# Sensor_Board.net
KiCad netlist of a schematic drawn in Altium Designer
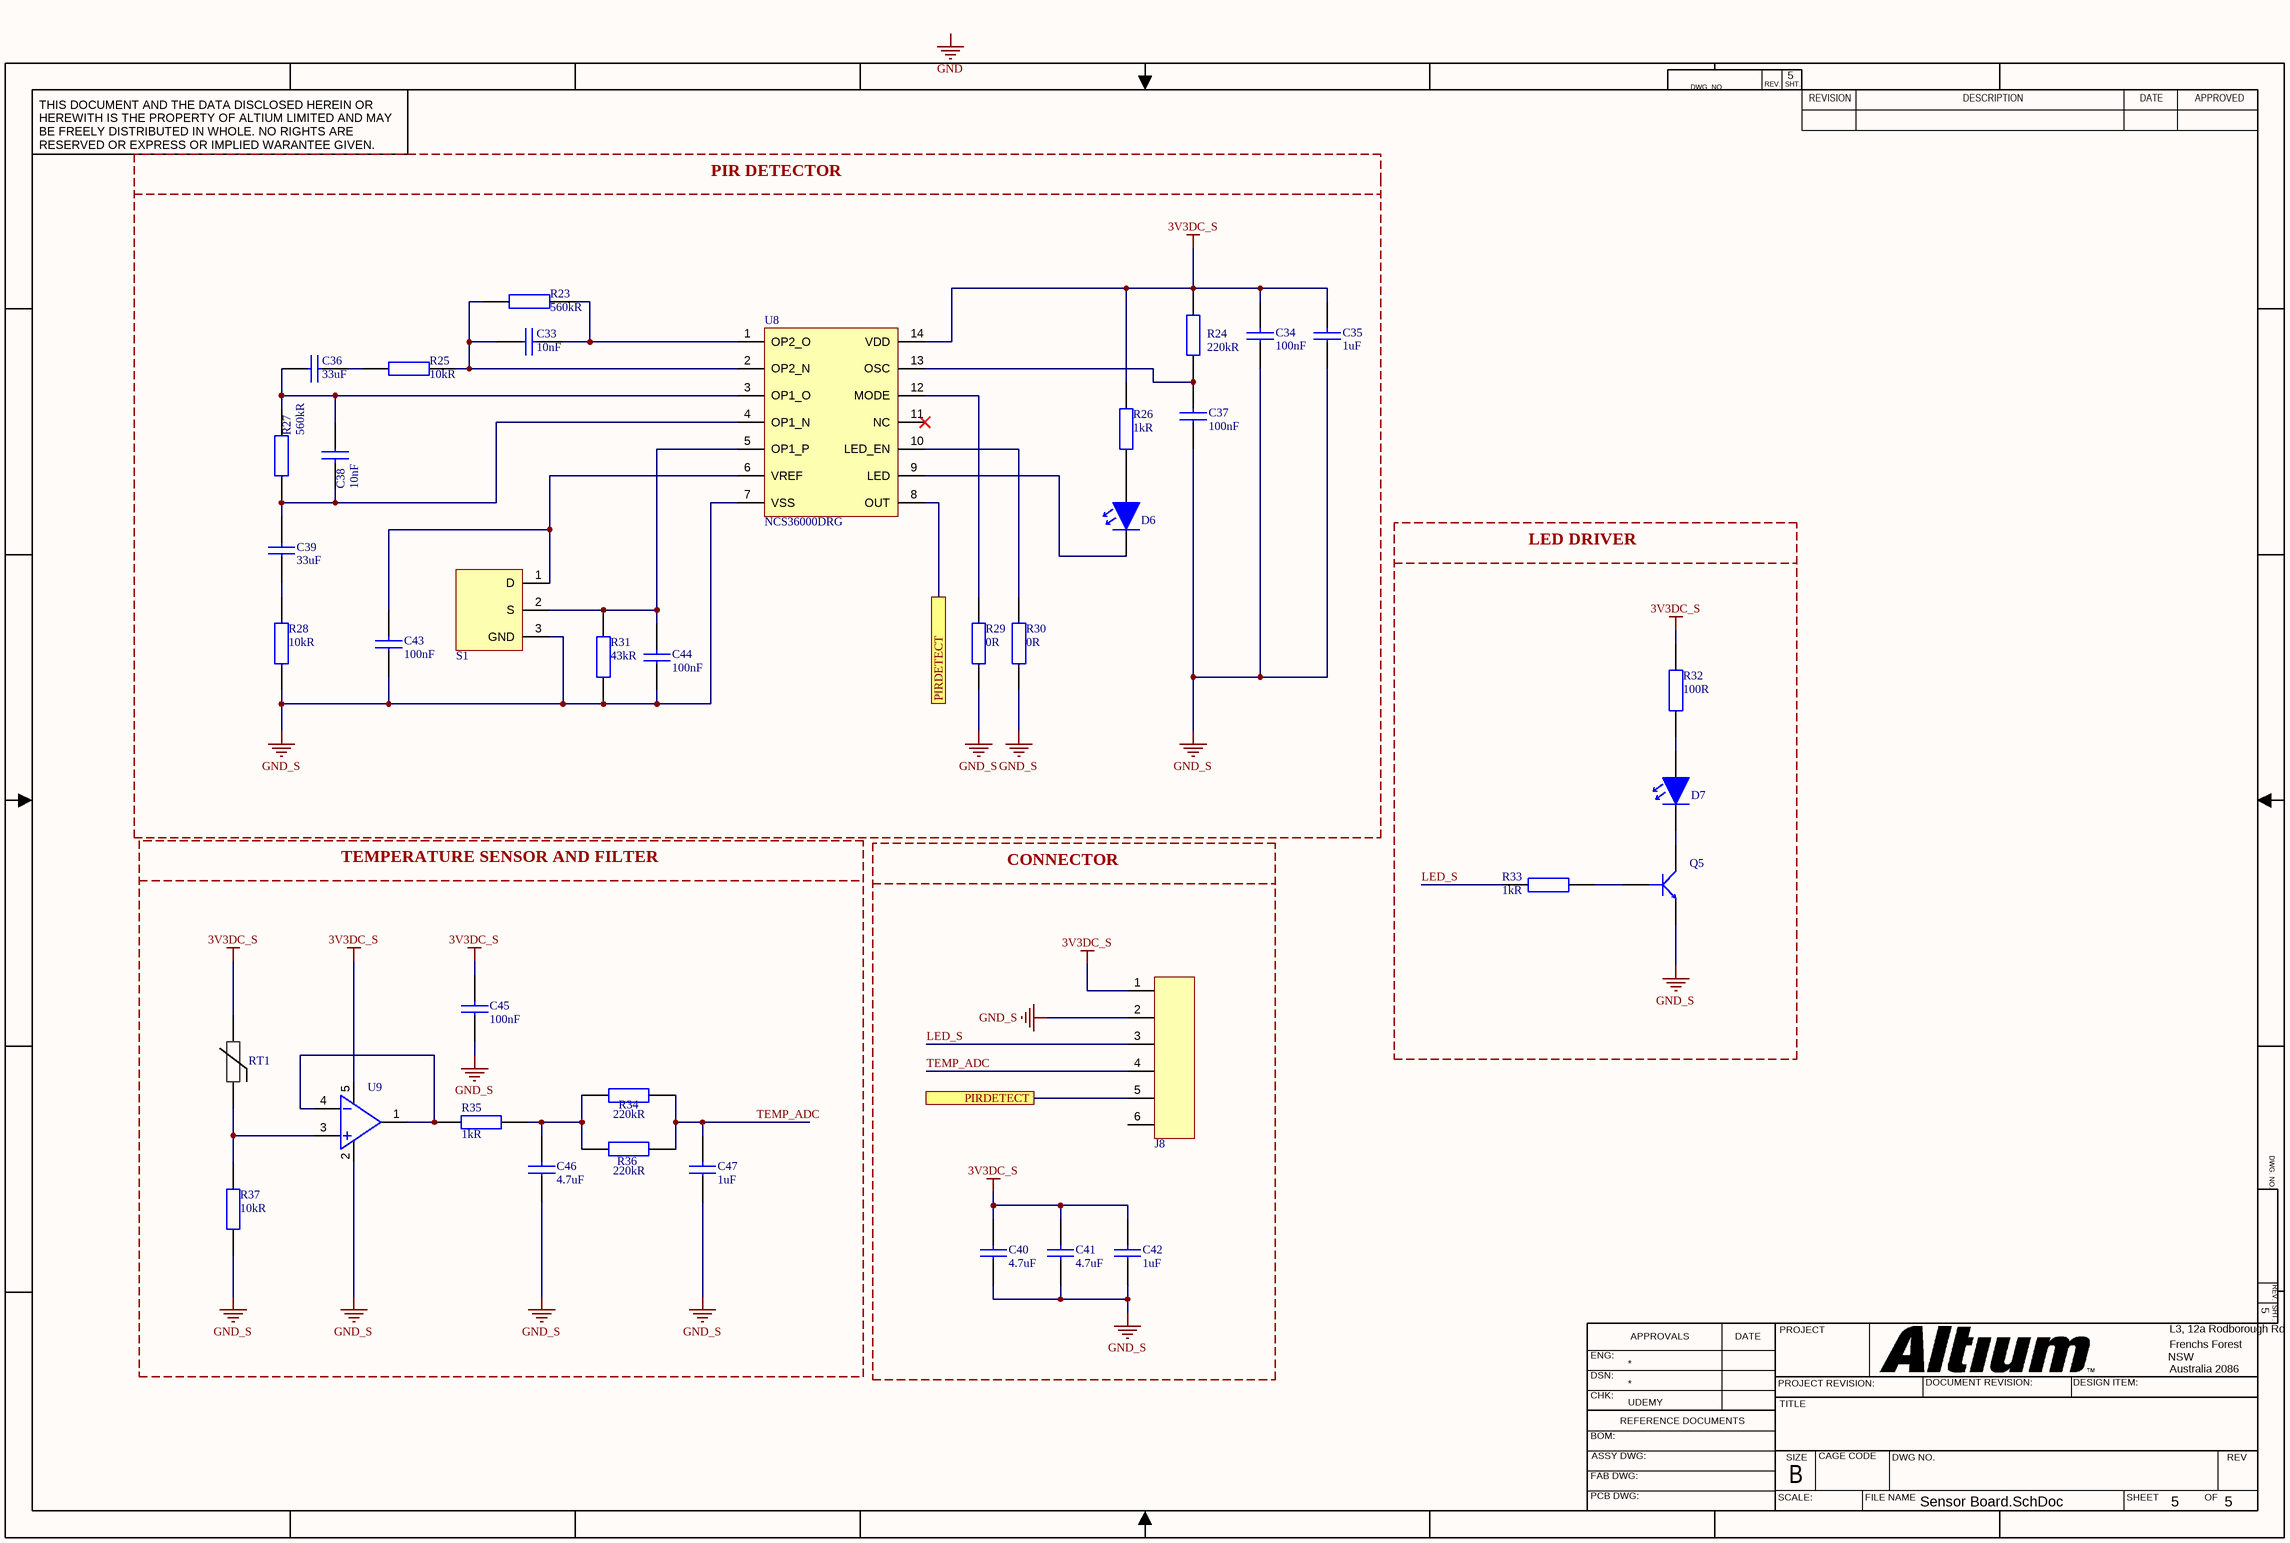
[diagram p0: Sensor Board.SchDoc]

(export (version "E")
  (design (tool "Eeschema 10.0.6"))
  (components
    (comp (ref "C33")
      (value "0603B103K160CT")
      (footprint "CAP_0603")
      (description "CAP CER 10nF %10 0603")
      (fields
        (field (name "MANUFACTURER") "Walsin Technologies")
        (field (name "TOLERANCE") "10%")
        (field (name "CAPACITANCE") "10nF")
        (field (name "DESIGNED BY") "BERK")
      )
      (libsource (lib "UDEMY_Library") (part "CAP CER 10nF 0603"))
    )
    (comp (ref "C34")
      (value "C0603C104K5RACTU")
      (footprint "CAP_0603")
      (description "CAP CER 100nF %10 0603 SMD")
      (fields
        (field (name "MANUFACTURER") "KEMET")
        (field (name "TOLERANCE") "10%")
        (field (name "CAPACITANCE") "100nF")
        (field (name "DESIGNED BY") "BERK")
      )
      (libsource (lib "UDEMY_Library") (part "CAP CER 100nF 0603"))
    )
    (comp (ref "C35")
      (value "CL21B105KBFNNNE")
      (footprint "CAP_0805")
      (description "CAP CER 1uF %10 0805")
      (fields
        (field (name "MANUFACTURER") "Samsung")
        (field (name "TOLERANCE") "10%")
        (field (name "CAPACITANCE") "1uF")
        (field (name "DESIGNED BY") "BERK")
      )
      (libsource (lib "UDEMY_Library") (part "CAP CER 1uF 0805"))
    )
    (comp (ref "C36")
      (value "C3216X5R1E336M160AC")
      (footprint "CAP_1206")
      (description "CAP CER 33uF %20 1206 SMD")
      (fields
        (field (name "MANUFACTURER") "TDK")
        (field (name "TOLERANCE") "20%")
        (field (name "CAPACITANCE") "33uF")
        (field (name "DESIGNED BY") "BERK")
      )
      (libsource (lib "UDEMY_Library") (part "CAP CER 33uF 1206"))
    )
    (comp (ref "C37")
      (value "C0603C104K5RACTU")
      (footprint "CAP_0603")
      (description "CAP CER 100nF %10 0603 SMD")
      (fields
        (field (name "MANUFACTURER") "KEMET")
        (field (name "TOLERANCE") "10%")
        (field (name "CAPACITANCE") "100nF")
        (field (name "DESIGNED BY") "BERK")
      )
      (libsource (lib "UDEMY_Library") (part "CAP CER 100nF 0603"))
    )
    (comp (ref "C38")
      (value "0603B103K160CT")
      (footprint "CAP_0603")
      (description "CAP CER 10nF %10 0603")
      (fields
        (field (name "MANUFACTURER") "Walsin Technologies")
        (field (name "TOLERANCE") "10%")
        (field (name "CAPACITANCE") "10nF")
        (field (name "DESIGNED BY") "BERK")
      )
      (libsource (lib "UDEMY_Library") (part "CAP CER 10nF 0603"))
    )
    (comp (ref "C39")
      (value "C3216X5R1E336M160AC")
      (footprint "CAP_1206")
      (description "CAP CER 33uF %20 1206 SMD")
      (fields
        (field (name "MANUFACTURER") "TDK")
        (field (name "TOLERANCE") "20%")
        (field (name "CAPACITANCE") "33uF")
        (field (name "DESIGNED BY") "BERK")
      )
      (libsource (lib "UDEMY_Library") (part "CAP CER 33uF 1206"))
    )
    (comp (ref "C40")
      (value "CL21A475KAQNNNE")
      (footprint "CAP_0805")
      (description "CAP CER 4.7uF %10 0805")
      (fields
        (field (name "MANUFACTURER") "Samsung")
        (field (name "TOLERANCE") "10%")
        (field (name "CAPACITANCE") "4.7uF")
        (field (name "DESIGNED BY") "BERK")
      )
      (libsource (lib "UDEMY_Library") (part "CAP CER 4.7uF 0805"))
    )
    (comp (ref "C41")
      (value "CL21A475KAQNNNE")
      (footprint "CAP_0805")
      (description "CAP CER 4.7uF %10 0805")
      (fields
        (field (name "MANUFACTURER") "Samsung")
        (field (name "TOLERANCE") "10%")
        (field (name "CAPACITANCE") "4.7uF")
        (field (name "DESIGNED BY") "BERK")
      )
      (libsource (lib "UDEMY_Library") (part "CAP CER 4.7uF 0805"))
    )
    (comp (ref "C42")
      (value "CL21B105KBFNNNE")
      (footprint "CAP_0805")
      (description "CAP CER 1uF %10 0805")
      (fields
        (field (name "MANUFACTURER") "Samsung")
        (field (name "TOLERANCE") "10%")
        (field (name "CAPACITANCE") "1uF")
        (field (name "DESIGNED BY") "BERK")
      )
      (libsource (lib "UDEMY_Library") (part "CAP CER 1uF 0805"))
    )
    (comp (ref "C43")
      (value "C0603C104K5RACTU")
      (footprint "CAP_0603")
      (description "CAP CER 100nF %10 0603 SMD")
      (fields
        (field (name "MANUFACTURER") "KEMET")
        (field (name "TOLERANCE") "10%")
        (field (name "CAPACITANCE") "100nF")
        (field (name "DESIGNED BY") "BERK")
      )
      (libsource (lib "UDEMY_Library") (part "CAP CER 100nF 0603"))
    )
    (comp (ref "C44")
      (value "C0603C104K5RACTU")
      (footprint "CAP_0603")
      (description "CAP CER 100nF %10 0603 SMD")
      (fields
        (field (name "MANUFACTURER") "KEMET")
        (field (name "TOLERANCE") "10%")
        (field (name "CAPACITANCE") "100nF")
        (field (name "DESIGNED BY") "BERK")
      )
      (libsource (lib "UDEMY_Library") (part "CAP CER 100nF 0603"))
    )
    (comp (ref "C45")
      (value "C0603C104K5RACTU")
      (footprint "CAP_0603")
      (description "CAP CER 100nF %10 0603 SMD")
      (fields
        (field (name "MANUFACTURER") "KEMET")
        (field (name "TOLERANCE") "10%")
        (field (name "CAPACITANCE") "100nF")
        (field (name "DESIGNED BY") "BERK")
      )
      (libsource (lib "UDEMY_Library") (part "CAP CER 100nF 0603"))
    )
    (comp (ref "C46")
      (value "CL21A475KAQNNNE")
      (footprint "CAP_0805")
      (description "CAP CER 4.7uF %10 0805")
      (fields
        (field (name "MANUFACTURER") "Samsung")
        (field (name "TOLERANCE") "10%")
        (field (name "CAPACITANCE") "4.7uF")
        (field (name "DESIGNED BY") "BERK")
      )
      (libsource (lib "UDEMY_Library") (part "CAP CER 4.7uF 0805"))
    )
    (comp (ref "C47")
      (value "CL21B105KBFNNNE")
      (footprint "CAP_0805")
      (description "CAP CER 1uF %10 0805")
      (fields
        (field (name "MANUFACTURER") "Samsung")
        (field (name "TOLERANCE") "10%")
        (field (name "CAPACITANCE") "1uF")
        (field (name "DESIGNED BY") "BERK")
      )
      (libsource (lib "UDEMY_Library") (part "CAP CER 1uF 0805"))
    )
    (comp (ref "D6")
      (value "LTST-C171GKT")
      (footprint "LED_GREEN_0805")
      (description "Green 0805 130 º Min 5 mcd Typical 12 mcd Water Clear Lens SMT LED")
      (fields (field (name "MANUFACTURER") "Vishay Lite-On") (field (name "DESIGNED BY") "BERK"))
      (libsource (lib "UDEMY_Library") (part "LED GREEN 0805"))
    )
    (comp (ref "D7")
      (value "LH R974-LP-1")
      (footprint "LED_RED_0805")
      (description "LED Uni-Color Hyper Red 660nm 2-Pin Chip 0805(2012Metric) T/R")
      (fields (field (name "MANUFACTURER") "Osram Opto") (field (name "DESIGNED BY") "BERK"))
      (libsource (lib "UDEMY_Library") (part "LED RED 0805"))
    )
    (comp (ref "J8")
      (value "64800611622")
      (footprint "64800611622")
      (description "1.50mm 6PIN Connector")
      (fields (field (name "MANUFACTURER") "Wurth Electronics"))
      (libsource (lib "UDEMY_Library") (part "64800611622_conn_6pin"))
    )
    (comp (ref "Q5")
      (value "MMBT3904-7-F")
      (footprint "SOT-23F")
      (description "Transistor General Purpose BJT NPN 40 Volt 0.2A Automotive 3-Pin SOT-23")
      (fields (field (name "MANUFACTURER") "Diodes Zetex") (field (name "DESIGNED BY") "BERK"))
      (libsource (lib "UDEMY_Library") (part "MMBT3904-7-F"))
    )
    (comp (ref "R23")
      (value "RC0603JR-07560KL")
      (footprint "RES_0603")
      (description "RES SMD 560K OHM 5% 1/10W 0603")
      (fields
        (field (name "MANUFACTURER") "Yageo")
        (field (name "TOLERANCE") "5%")
        (field (name "RESISTANCE") "560kR")
        (field (name "DESIGNED BY") "BERK")
      )
      (libsource (lib "UDEMY_Library") (part "RES 560K OHM 0603"))
    )
    (comp (ref "R24")
      (value "RC0603JR-07220KL")
      (footprint "RES_0603")
      (description "RES 220K %5 OHM 0603 SMD")
      (fields
        (field (name "MANUFACTURER") "Yageo")
        (field (name "TOLERANCE") "5%")
        (field (name "RESISTANCE") "220kR")
      )
      (libsource (lib "") (part "RES 220K OHM 0603_1"))
    )
    (comp (ref "R25")
      (value "RC0603FR-0710KL")
      (footprint "RES_0603")
      (description "RES 10K %1 OHM 0603 SMD")
      (fields
        (field (name "MANUFACTURER") "Yageo")
        (field (name "TOLERANCE") "1%")
        (field (name "RESISTANCE") "10kR")
        (field (name "DESIGNED BY") "BERK")
      )
      (libsource (lib "") (part "RES 10K OHM 0603_1"))
    )
    (comp (ref "R26")
      (value "RC0603FR-0710KL")
      (footprint "RES_0603")
      (description "RES 1K %1 OHM 0603 SMD")
      (fields
        (field (name "MANUFACTURER") "Yageo")
        (field (name "MANUFACTURER PART NUMBER") "RC0603JR-071KL")
        (field (name "RESISTANCE") "1kR")
        (field (name "DESIGNED BY") "BERK")
      )
      (libsource (lib "") (part "RES 1K OHM 0603_1"))
    )
    (comp (ref "R27")
      (value "RC0603JR-07560KL")
      (footprint "RES_0603")
      (description "RES SMD 560K OHM 5% 1/10W 0603")
      (fields
        (field (name "MANUFACTURER") "Yageo")
        (field (name "TOLERANCE") "5%")
        (field (name "RESISTANCE") "560kR")
        (field (name "DESIGNED BY") "BERK")
      )
      (libsource (lib "") (part "RES 560K OHM 0603_1"))
    )
    (comp (ref "R28")
      (value "RC0603FR-0710KL")
      (footprint "RES_0603")
      (description "RES 10K %1 OHM 0603 SMD")
      (fields
        (field (name "MANUFACTURER") "Yageo")
        (field (name "TOLERANCE") "1%")
        (field (name "RESISTANCE") "10kR")
        (field (name "DESIGNED BY") "BERK")
      )
      (libsource (lib "UDEMY_Library") (part "RES 10K OHM 0603"))
    )
    (comp (ref "R29")
      (value "RC0603JR-070RL")
      (footprint "RES_0603")
      (description "RES 0 %1 OHM 0603 SMD")
      (fields
        (field (name "MANUFACTURER") "Yageo")
        (field (name "TOLERANCE") "1%")
        (field (name "RESISTANCE") "0R")
        (field (name "DESIGNED BY") "BERK")
      )
      (libsource (lib "UDEMY_Library") (part "RES 0 OHM 0603"))
    )
    (comp (ref "R30")
      (value "RC0603JR-070RL")
      (footprint "RES_0603")
      (description "RES 0 %1 OHM 0603 SMD")
      (fields
        (field (name "MANUFACTURER") "Yageo")
        (field (name "TOLERANCE") "1%")
        (field (name "RESISTANCE") "0R")
        (field (name "DESIGNED BY") "BERK")
      )
      (libsource (lib "UDEMY_Library") (part "RES 0 OHM 0603"))
    )
    (comp (ref "R31")
      (value "RC0603JR-0743KL")
      (footprint "RES_0603")
      (description "RES 43K %5 OHM 0603 SMD")
      (fields
        (field (name "MANUFACTURER") "Yageo")
        (field (name "TOLERANCE") "5%")
        (field (name "RESISTANCE") "43kR")
        (field (name "DESIGNED BY") "BERK")
      )
      (libsource (lib "UDEMY_Library") (part "RES 43K OHM 0603"))
    )
    (comp (ref "R32")
      (value "RC0603JR-07100RL")
      (footprint "RES_0603")
      (description "RES 100 %5 OHM 0603 SMD")
      (fields
        (field (name "MANUFACTURER") "Yageo")
        (field (name "TOLERANCE") "5%")
        (field (name "RESISTANCE") "100R")
        (field (name "DESIGNED BY") "BERK")
      )
      (libsource (lib "UDEMY_Library") (part "RES 100 OHM 0603"))
    )
    (comp (ref "R33")
      (value "RC0603FR-0710KL")
      (footprint "RES_0603")
      (description "RES 1K %1 OHM 0603 SMD")
      (fields
        (field (name "MANUFACTURER") "Yageo")
        (field (name "MANUFACTURER PART NUMBER") "RC0603JR-071KL")
        (field (name "RESISTANCE") "1kR")
        (field (name "DESIGNED BY") "BERK")
      )
      (libsource (lib "UDEMY_Library") (part "RES 1K OHM 0603"))
    )
    (comp (ref "R34")
      (value "RC0603JR-07220KL")
      (footprint "RES_0603")
      (description "RES 220K %5 OHM 0603 SMD")
      (fields
        (field (name "MANUFACTURER") "Yageo")
        (field (name "TOLERANCE") "5%")
        (field (name "RESISTANCE") "220kR")
      )
      (libsource (lib "UDEMY_Library") (part "RES 220K OHM 0603"))
    )
    (comp (ref "R35")
      (value "RC0603FR-0710KL")
      (footprint "RES_0603")
      (description "RES 1K %1 OHM 0603 SMD")
      (fields
        (field (name "MANUFACTURER") "Yageo")
        (field (name "MANUFACTURER PART NUMBER") "RC0603JR-071KL")
        (field (name "RESISTANCE") "1kR")
        (field (name "DESIGNED BY") "BERK")
      )
      (libsource (lib "UDEMY_Library") (part "RES 1K OHM 0603"))
    )
    (comp (ref "R36")
      (value "RC0603JR-07220KL")
      (footprint "RES_0603")
      (description "RES 220K %5 OHM 0603 SMD")
      (fields
        (field (name "MANUFACTURER") "Yageo")
        (field (name "TOLERANCE") "5%")
        (field (name "RESISTANCE") "220kR")
      )
      (libsource (lib "UDEMY_Library") (part "RES 220K OHM 0603"))
    )
    (comp (ref "R37")
      (value "RC0603FR-0710KL")
      (footprint "RES_0603")
      (description "RES 10K %1 OHM 0603 SMD")
      (fields
        (field (name "MANUFACTURER") "Yageo")
        (field (name "TOLERANCE") "1%")
        (field (name "RESISTANCE") "10kR")
        (field (name "DESIGNED BY") "BERK")
      )
      (libsource (lib "UDEMY_Library") (part "RES 10K OHM 0603"))
    )
    (comp (ref "RT1")
      (value "TFPT1206L1002FM")
      (footprint "RES_1206")
      (description "Thermistor PTC 10K Ohm 1% 1206")
      (fields
        (field (name "MANUFACTURER") "Vishay Dale")
        (field (name "TOLERANCE") "1%")
        (field (name "DESIGNED BY") "BERK")
      )
      (libsource (lib "UDEMY_Library") (part "TFPT1206L1002FM"))
    )
    (comp (ref "S1")
      (value "LHI 878/3902")
      (footprint "LHI 878")
      (description "SENSOR PYRO DETECTOR DUAL MOTION")
      (fields (field (name "DESIGNED BY") "BERK"))
      (libsource (lib "UDEMY_Library") (part "LHI 878/3902"))
    )
    (comp (ref "U8")
      (value "NCS36000DRG")
      (footprint "SOIC14")
      (description "PIR Controller Low Noise Amplifiers and LDO Regulator 14-Pin SOIC N T/R")
      (fields (field (name "MANUFACTURER") "ON Semiconductor") (field (name "DESIGNED BY") "BERK"))
      (libsource (lib "UDEMY_Library") (part "NCS36000"))
    )
    (comp (ref "U9")
      (value "OPA314AIDBVR")
      (footprint "SOT23-5")
      (description "Op Amp OPA314")
      (fields (field (name "MANUFACTURER") "Texas Instruments") (field (name "DESIGNED BY") "BERK"))
      (libsource (lib "UDEMY_Library") (part "OPA314"))
    )
  )
  (nets
    (net (code "1") (name "/LED_S") (class "Default")
      (node (ref "J8") (pin "3") (pintype "power_in"))
      (node (ref "R33") (pin "1") (pinfunction "1_1") (pintype "passive"))
    )
    (net (code "2") (name "/PIRDETECT") (class "Default")
      (node (ref "J8") (pin "5") (pintype "power_in"))
      (node (ref "U8") (pin "8") (pinfunction "OUT_8") (pintype "passive"))
    )
    (net (code "3") (name "/TEMP_ADC") (class "Default")
      (node (ref "C47") (pin "2") (pinfunction "2_2") (pintype "passive"))
      (node (ref "J8") (pin "4") (pintype "power_in"))
      (node (ref "R34") (pin "2") (pinfunction "2_2") (pintype "passive"))
      (node (ref "R36") (pin "2") (pinfunction "2_2") (pintype "passive"))
    )
    (net (code "4") (name "3V3DC_S") (class "Default")
      (node (ref "C34") (pin "2") (pinfunction "2_2") (pintype "passive"))
      (node (ref "C35") (pin "2") (pinfunction "2_2") (pintype "passive"))
      (node (ref "C40") (pin "2") (pinfunction "2_2") (pintype "passive"))
      (node (ref "C41") (pin "2") (pinfunction "2_2") (pintype "passive"))
      (node (ref "C42") (pin "2") (pinfunction "2_2") (pintype "passive"))
      (node (ref "C45") (pin "2") (pinfunction "2_2") (pintype "passive"))
      (node (ref "J8") (pin "1") (pintype "power_in"))
      (node (ref "R24") (pin "2") (pinfunction "2_2") (pintype "passive"))
      (node (ref "R26") (pin "2") (pinfunction "2_2") (pintype "passive"))
      (node (ref "R32") (pin "2") (pinfunction "2_2") (pintype "passive"))
      (node (ref "RT1") (pin "2") (pinfunction "2_2") (pintype "passive"))
      (node (ref "U8") (pin "14") (pinfunction "VDD_14") (pintype "passive"))
      (node (ref "U9") (pin "5") (pinfunction "5_5") (pintype "passive"))
    )
    (net (code "6") (name "GND_S") (class "Default")
      (node (ref "C34") (pin "1") (pinfunction "1_1") (pintype "passive"))
      (node (ref "C35") (pin "1") (pinfunction "1_1") (pintype "passive"))
      (node (ref "C37") (pin "1") (pinfunction "1_1") (pintype "passive"))
      (node (ref "C40") (pin "1") (pinfunction "1_1") (pintype "passive"))
      (node (ref "C41") (pin "1") (pinfunction "1_1") (pintype "passive"))
      (node (ref "C42") (pin "1") (pinfunction "1_1") (pintype "passive"))
      (node (ref "C43") (pin "1") (pinfunction "1_1") (pintype "passive"))
      (node (ref "C44") (pin "1") (pinfunction "1_1") (pintype "passive"))
      (node (ref "C45") (pin "1") (pinfunction "1_1") (pintype "passive"))
      (node (ref "C46") (pin "1") (pinfunction "1_1") (pintype "passive"))
      (node (ref "C47") (pin "1") (pinfunction "1_1") (pintype "passive"))
      (node (ref "J8") (pin "2") (pintype "power_in"))
      (node (ref "Q5") (pin "2") (pinfunction "E_2") (pintype "power_in"))
      (node (ref "R28") (pin "1") (pinfunction "1_1") (pintype "passive"))
      (node (ref "R29") (pin "1") (pinfunction "1_1") (pintype "passive"))
      (node (ref "R30") (pin "1") (pinfunction "1_1") (pintype "passive"))
      (node (ref "R31") (pin "1") (pinfunction "1_1") (pintype "passive"))
      (node (ref "R37") (pin "1") (pinfunction "1_1") (pintype "passive"))
      (node (ref "S1") (pin "3") (pinfunction "GND_3") (pintype "passive"))
      (node (ref "U8") (pin "7") (pinfunction "VSS_7") (pintype "passive"))
      (node (ref "U9") (pin "2") (pinfunction "2_2") (pintype "passive"))
    )
    (net (code "7") (name "Net-(C36-Pad2)") (class "Default")
      (node (ref "C36") (pin "2") (pinfunction "2_2") (pintype "passive"))
      (node (ref "R25") (pin "1") (pinfunction "1_1") (pintype "passive"))
    )
    (net (code "8") (name "Net-(C39-Pad1)") (class "Default")
      (node (ref "C39") (pin "1") (pinfunction "1_1") (pintype "passive"))
      (node (ref "R28") (pin "2") (pinfunction "2_2") (pintype "passive"))
    )
    (net (code "9") (name "Net-(C46-Pad2)") (class "Default")
      (node (ref "C46") (pin "2") (pinfunction "2_2") (pintype "passive"))
      (node (ref "R34") (pin "1") (pinfunction "1_1") (pintype "passive"))
      (node (ref "R35") (pin "2") (pinfunction "2_2") (pintype "passive"))
      (node (ref "R36") (pin "1") (pinfunction "1_1") (pintype "passive"))
    )
    (net (code "10") (name "Net-(D6-Pad2)") (class "Default")
      (node (ref "D6") (pin "2") (pinfunction "2_2") (pintype "power_in"))
      (node (ref "R26") (pin "1") (pinfunction "1_1") (pintype "passive"))
    )
    (net (code "11") (name "Net-(D7-Pad2)") (class "Default")
      (node (ref "D7") (pin "2") (pinfunction "2_2") (pintype "power_in"))
      (node (ref "R32") (pin "1") (pinfunction "1_1") (pintype "passive"))
    )
    (net (code "12") (name "Net-(Q5-B)") (class "Default")
      (node (ref "Q5") (pin "1") (pinfunction "B_1") (pintype "power_in"))
      (node (ref "R33") (pin "2") (pinfunction "2_2") (pintype "passive"))
    )
    (net (code "13") (name "Net-(Q5-C)") (class "Default")
      (node (ref "D7") (pin "1") (pinfunction "1_1") (pintype "power_in"))
      (node (ref "Q5") (pin "3") (pinfunction "C_3") (pintype "power_in"))
    )
    (net (code "14") (name "Net-(R35-Pad1)") (class "Default")
      (node (ref "R35") (pin "1") (pinfunction "1_1") (pintype "passive"))
      (node (ref "U9") (pin "1") (pinfunction "1_1") (pintype "passive"))
      (node (ref "U9") (pin "4") (pinfunction "4_4") (pintype "passive"))
    )
    (net (code "15") (name "Net-(R37-Pad2)") (class "Default")
      (node (ref "R37") (pin "2") (pinfunction "2_2") (pintype "passive"))
      (node (ref "RT1") (pin "1") (pinfunction "1_1") (pintype "passive"))
      (node (ref "U9") (pin "3") (pinfunction "3_3") (pintype "passive"))
    )
    (net (code "16") (name "Net-(S1-D)") (class "Default")
      (node (ref "C43") (pin "2") (pinfunction "2_2") (pintype "passive"))
      (node (ref "S1") (pin "1") (pinfunction "D_1") (pintype "passive"))
      (node (ref "U8") (pin "6") (pinfunction "VREF_6") (pintype "passive"))
    )
    (net (code "17") (name "Net-(S1-S)") (class "Default")
      (node (ref "C44") (pin "2") (pinfunction "2_2") (pintype "passive"))
      (node (ref "R31") (pin "2") (pinfunction "2_2") (pintype "passive"))
      (node (ref "S1") (pin "2") (pinfunction "S_2") (pintype "passive"))
      (node (ref "U8") (pin "5") (pinfunction "OP1_P_5") (pintype "passive"))
    )
    (net (code "18") (name "Net-(U8-LED)") (class "Default")
      (node (ref "D6") (pin "1") (pinfunction "1_1") (pintype "power_in"))
      (node (ref "U8") (pin "9") (pinfunction "LED_9") (pintype "passive"))
    )
    (net (code "19") (name "Net-(U8-LED_EN)") (class "Default")
      (node (ref "R30") (pin "2") (pinfunction "2_2") (pintype "passive"))
      (node (ref "U8") (pin "10") (pinfunction "LED_EN_10") (pintype "passive"))
    )
    (net (code "20") (name "Net-(U8-MODE)") (class "Default")
      (node (ref "R29") (pin "2") (pinfunction "2_2") (pintype "passive"))
      (node (ref "U8") (pin "12") (pinfunction "MODE_12") (pintype "passive"))
    )
    (net (code "21") (name "Net-(U8-OP1_N)") (class "Default")
      (node (ref "C38") (pin "2") (pinfunction "2_2") (pintype "passive"))
      (node (ref "C39") (pin "2") (pinfunction "2_2") (pintype "passive"))
      (node (ref "R27") (pin "1") (pinfunction "1_1") (pintype "passive"))
      (node (ref "U8") (pin "4") (pinfunction "OP1_N_4") (pintype "passive"))
    )
    (net (code "22") (name "Net-(U8-OP1_O)") (class "Default")
      (node (ref "C36") (pin "1") (pinfunction "1_1") (pintype "passive"))
      (node (ref "C38") (pin "1") (pinfunction "1_1") (pintype "passive"))
      (node (ref "R27") (pin "2") (pinfunction "2_2") (pintype "passive"))
      (node (ref "U8") (pin "3") (pinfunction "OP1_O_3") (pintype "passive"))
    )
    (net (code "23") (name "Net-(U8-OP2_N)") (class "Default")
      (node (ref "C33") (pin "1") (pinfunction "1_1") (pintype "passive"))
      (node (ref "R23") (pin "1") (pinfunction "1_1") (pintype "passive"))
      (node (ref "R25") (pin "2") (pinfunction "2_2") (pintype "passive"))
      (node (ref "U8") (pin "2") (pinfunction "OP2_N_2") (pintype "passive"))
    )
    (net (code "24") (name "Net-(U8-OP2_O)") (class "Default")
      (node (ref "C33") (pin "2") (pinfunction "2_2") (pintype "passive"))
      (node (ref "R23") (pin "2") (pinfunction "2_2") (pintype "passive"))
      (node (ref "U8") (pin "1") (pinfunction "OP2_O_1") (pintype "passive"))
    )
    (net (code "25") (name "Net-(U8-OSC)") (class "Default")
      (node (ref "C37") (pin "2") (pinfunction "2_2") (pintype "passive"))
      (node (ref "R24") (pin "1") (pinfunction "1_1") (pintype "passive"))
      (node (ref "U8") (pin "13") (pinfunction "OSC_13") (pintype "passive"))
    )
    (net (code "26") (name "unconnected-(J8-Pad6)") (class "Default")
      (node (ref "J8") (pin "6") (pintype "power_in"))
    )
    (net (code "27") (name "unconnected-(U8-NC-Pad11)") (class "Default")
      (node (ref "U8") (pin "11") (pinfunction "NC_11") (pintype "passive+no_connect"))
    )
  )
)
